# Schematic.net
KiCad netlist of a schematic drawn in EasyEDA
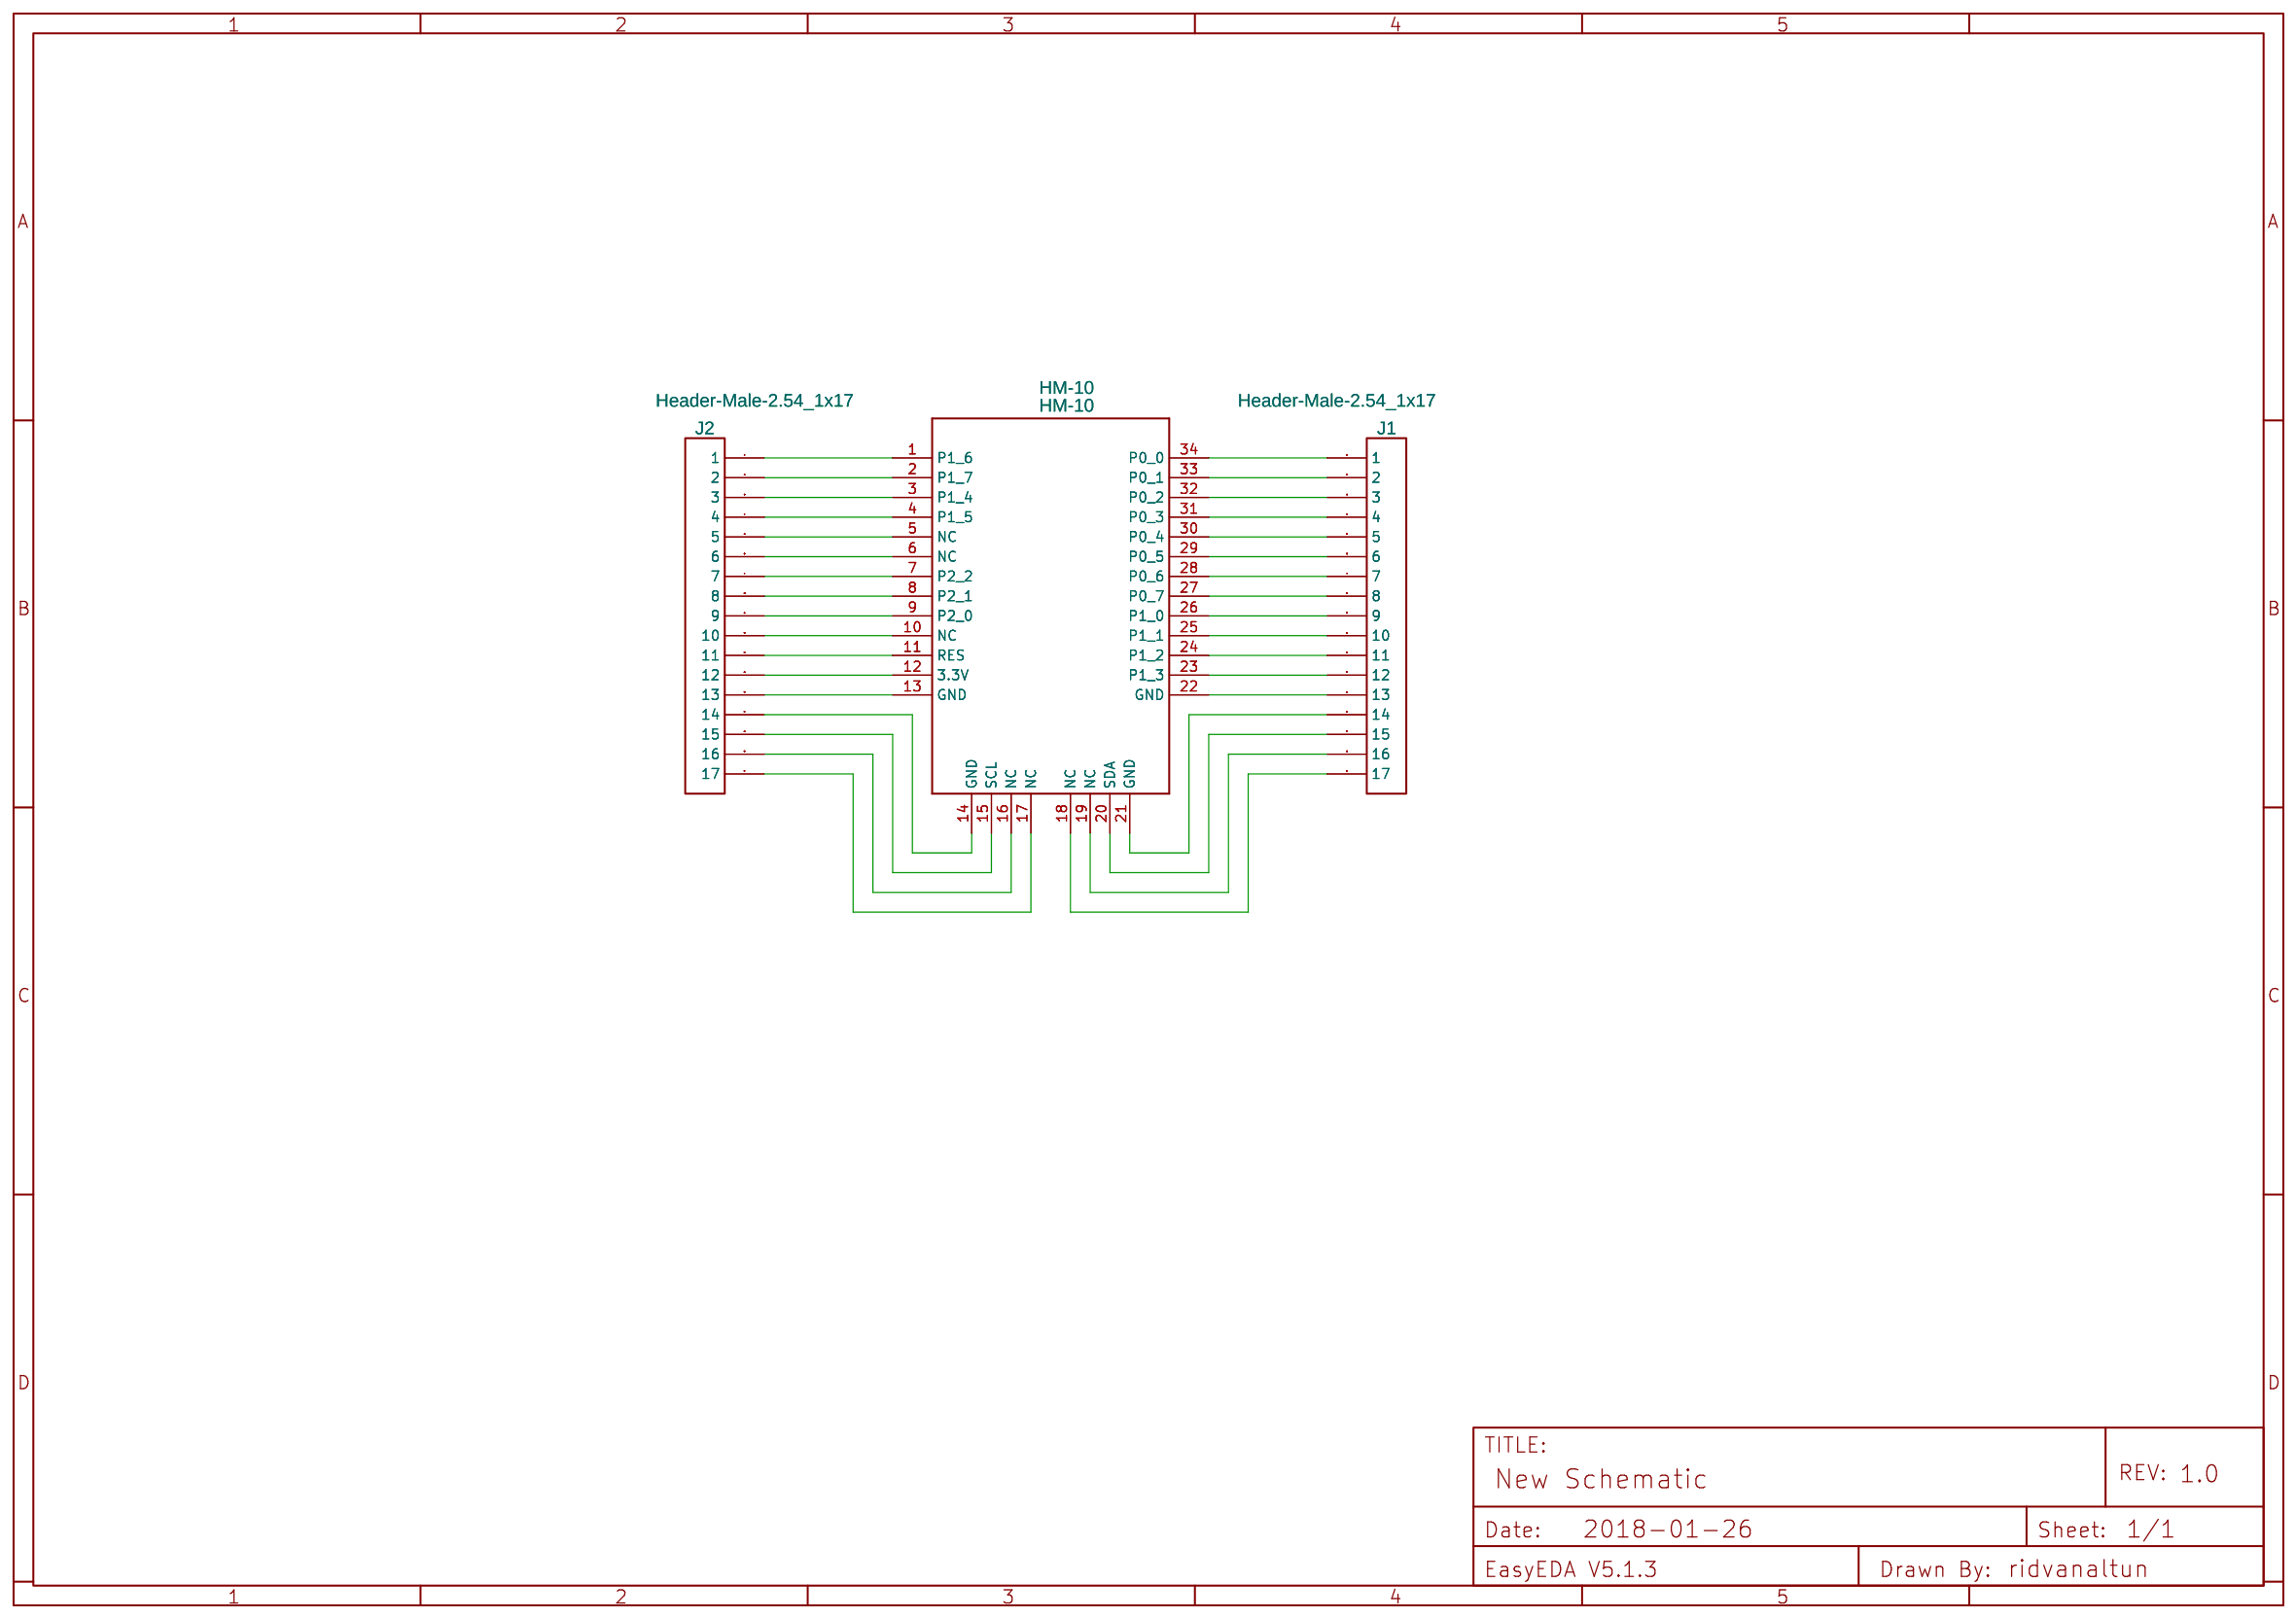
[diagram p0: schematic sheet]

(export (version "E")
  (design (tool "Eeschema 10.0.6"))
  (components
    (comp (ref "HM-10")
      (value "HM-10")
      (fields (field (name "BOM_Manufacturer Part") "?"))
      (libsource (lib "") (part "Unknown_525_315"))
    )
    (comp (ref "J1")
      (value "Header-Male-2.54_1x17")
      (fields (field (name "BOM_Manufacturer Part") "2.54mm 1*17PHeader"))
      (libsource (lib "") (part "Unknown_675_315"))
    )
    (comp (ref "J2")
      (value "Header-Male-2.54_1x17")
      (fields (field (name "BOM_Manufacturer Part") "2.54mm 1*17PHeader"))
      (libsource (lib "") (part "Unknown_370_315"))
    )
  )
  (nets
    (net (code "1") (name "Net-(HM-10-3.3V)") (class "Default")
      (node (ref "HM-10") (pin "12") (pinfunction "3.3V_12") (pintype "unspecified"))
      (node (ref "J2") (pin "12") (pinfunction "12_12") (pintype "input"))
    )
    (net (code "2") (name "Net-(HM-10-GND-Pad13)") (class "Default")
      (node (ref "HM-10") (pin "13") (pinfunction "GND_13") (pintype "unspecified"))
      (node (ref "J2") (pin "13") (pinfunction "13_13") (pintype "input"))
    )
    (net (code "3") (name "Net-(HM-10-GND-Pad14)") (class "Default")
      (node (ref "HM-10") (pin "14") (pinfunction "GND_14") (pintype "unspecified"))
      (node (ref "J2") (pin "14") (pinfunction "14_14") (pintype "input"))
    )
    (net (code "4") (name "Net-(HM-10-GND-Pad21)") (class "Default")
      (node (ref "HM-10") (pin "21") (pinfunction "GND_21") (pintype "unspecified"))
      (node (ref "J1") (pin "14") (pinfunction "14_14") (pintype "input"))
    )
    (net (code "5") (name "Net-(HM-10-GND-Pad22)") (class "Default")
      (node (ref "HM-10") (pin "22") (pinfunction "GND_22") (pintype "unspecified"))
      (node (ref "J1") (pin "13") (pinfunction "13_13") (pintype "input"))
    )
    (net (code "6") (name "Net-(HM-10-NC-Pad5)") (class "Default")
      (node (ref "HM-10") (pin "5") (pinfunction "NC_5") (pintype "unspecified"))
      (node (ref "J2") (pin "5") (pinfunction "5_5") (pintype "input"))
    )
    (net (code "7") (name "Net-(HM-10-NC-Pad6)") (class "Default")
      (node (ref "HM-10") (pin "6") (pinfunction "NC_6") (pintype "unspecified"))
      (node (ref "J2") (pin "6") (pinfunction "6_6") (pintype "input"))
    )
    (net (code "8") (name "Net-(HM-10-NC-Pad10)") (class "Default")
      (node (ref "HM-10") (pin "10") (pinfunction "NC_10") (pintype "unspecified"))
      (node (ref "J2") (pin "10") (pinfunction "10_10") (pintype "input"))
    )
    (net (code "9") (name "Net-(HM-10-NC-Pad16)") (class "Default")
      (node (ref "HM-10") (pin "16") (pinfunction "NC_16") (pintype "unspecified"))
      (node (ref "J2") (pin "16") (pinfunction "16_16") (pintype "input"))
    )
    (net (code "10") (name "Net-(HM-10-NC-Pad17)") (class "Default")
      (node (ref "HM-10") (pin "17") (pinfunction "NC_17") (pintype "unspecified"))
      (node (ref "J2") (pin "17") (pinfunction "17_17") (pintype "input"))
    )
    (net (code "11") (name "Net-(HM-10-NC-Pad18)") (class "Default")
      (node (ref "HM-10") (pin "18") (pinfunction "NC_18") (pintype "unspecified"))
      (node (ref "J1") (pin "17") (pinfunction "17_17") (pintype "input"))
    )
    (net (code "12") (name "Net-(HM-10-NC-Pad19)") (class "Default")
      (node (ref "HM-10") (pin "19") (pinfunction "NC_19") (pintype "unspecified"))
      (node (ref "J1") (pin "16") (pinfunction "16_16") (pintype "input"))
    )
    (net (code "13") (name "Net-(HM-10-P0_0)") (class "Default")
      (node (ref "HM-10") (pin "34") (pinfunction "P0_0_34") (pintype "unspecified"))
      (node (ref "J1") (pin "1") (pinfunction "1_1") (pintype "input"))
    )
    (net (code "14") (name "Net-(HM-10-P0_1)") (class "Default")
      (node (ref "HM-10") (pin "33") (pinfunction "P0_1_33") (pintype "unspecified"))
      (node (ref "J1") (pin "2") (pinfunction "2_2") (pintype "input"))
    )
    (net (code "15") (name "Net-(HM-10-P0_2)") (class "Default")
      (node (ref "HM-10") (pin "32") (pinfunction "P0_2_32") (pintype "unspecified"))
      (node (ref "J1") (pin "3") (pinfunction "3_3") (pintype "input"))
    )
    (net (code "16") (name "Net-(HM-10-P0_3)") (class "Default")
      (node (ref "HM-10") (pin "31") (pinfunction "P0_3_31") (pintype "unspecified"))
      (node (ref "J1") (pin "4") (pinfunction "4_4") (pintype "input"))
    )
    (net (code "17") (name "Net-(HM-10-P0_4)") (class "Default")
      (node (ref "HM-10") (pin "30") (pinfunction "P0_4_30") (pintype "unspecified"))
      (node (ref "J1") (pin "5") (pinfunction "5_5") (pintype "input"))
    )
    (net (code "18") (name "Net-(HM-10-P0_5)") (class "Default")
      (node (ref "HM-10") (pin "29") (pinfunction "P0_5_29") (pintype "unspecified"))
      (node (ref "J1") (pin "6") (pinfunction "6_6") (pintype "input"))
    )
    (net (code "19") (name "Net-(HM-10-P0_6)") (class "Default")
      (node (ref "HM-10") (pin "28") (pinfunction "P0_6_28") (pintype "unspecified"))
      (node (ref "J1") (pin "7") (pinfunction "7_7") (pintype "input"))
    )
    (net (code "20") (name "Net-(HM-10-P0_7)") (class "Default")
      (node (ref "HM-10") (pin "27") (pinfunction "P0_7_27") (pintype "unspecified"))
      (node (ref "J1") (pin "8") (pinfunction "8_8") (pintype "input"))
    )
    (net (code "21") (name "Net-(HM-10-P1_0)") (class "Default")
      (node (ref "HM-10") (pin "26") (pinfunction "P1_0_26") (pintype "unspecified"))
      (node (ref "J1") (pin "9") (pinfunction "9_9") (pintype "input"))
    )
    (net (code "22") (name "Net-(HM-10-P1_1)") (class "Default")
      (node (ref "HM-10") (pin "25") (pinfunction "P1_1_25") (pintype "unspecified"))
      (node (ref "J1") (pin "10") (pinfunction "10_10") (pintype "input"))
    )
    (net (code "23") (name "Net-(HM-10-P1_2)") (class "Default")
      (node (ref "HM-10") (pin "24") (pinfunction "P1_2_24") (pintype "unspecified"))
      (node (ref "J1") (pin "11") (pinfunction "11_11") (pintype "input"))
    )
    (net (code "24") (name "Net-(HM-10-P1_3)") (class "Default")
      (node (ref "HM-10") (pin "23") (pinfunction "P1_3_23") (pintype "unspecified"))
      (node (ref "J1") (pin "12") (pinfunction "12_12") (pintype "input"))
    )
    (net (code "25") (name "Net-(HM-10-P1_4)") (class "Default")
      (node (ref "HM-10") (pin "3") (pinfunction "P1_4_3") (pintype "unspecified"))
      (node (ref "J2") (pin "3") (pinfunction "3_3") (pintype "input"))
    )
    (net (code "26") (name "Net-(HM-10-P1_5)") (class "Default")
      (node (ref "HM-10") (pin "4") (pinfunction "P1_5_4") (pintype "unspecified"))
      (node (ref "J2") (pin "4") (pinfunction "4_4") (pintype "input"))
    )
    (net (code "27") (name "Net-(HM-10-P1_6)") (class "Default")
      (node (ref "HM-10") (pin "1") (pinfunction "P1_6_1") (pintype "unspecified"))
      (node (ref "J2") (pin "1") (pinfunction "1_1") (pintype "input"))
    )
    (net (code "28") (name "Net-(HM-10-P1_7)") (class "Default")
      (node (ref "HM-10") (pin "2") (pinfunction "P1_7_2") (pintype "unspecified"))
      (node (ref "J2") (pin "2") (pinfunction "2_2") (pintype "input"))
    )
    (net (code "29") (name "Net-(HM-10-P2_0)") (class "Default")
      (node (ref "HM-10") (pin "9") (pinfunction "P2_0_9") (pintype "unspecified"))
      (node (ref "J2") (pin "9") (pinfunction "9_9") (pintype "input"))
    )
    (net (code "30") (name "Net-(HM-10-P2_1)") (class "Default")
      (node (ref "HM-10") (pin "8") (pinfunction "P2_1_8") (pintype "unspecified"))
      (node (ref "J2") (pin "8") (pinfunction "8_8") (pintype "input"))
    )
    (net (code "31") (name "Net-(HM-10-P2_2)") (class "Default")
      (node (ref "HM-10") (pin "7") (pinfunction "P2_2_7") (pintype "unspecified"))
      (node (ref "J2") (pin "7") (pinfunction "7_7") (pintype "input"))
    )
    (net (code "32") (name "Net-(HM-10-RES)") (class "Default")
      (node (ref "HM-10") (pin "11") (pinfunction "RES_11") (pintype "unspecified"))
      (node (ref "J2") (pin "11") (pinfunction "11_11") (pintype "input"))
    )
    (net (code "33") (name "Net-(HM-10-SCL)") (class "Default")
      (node (ref "HM-10") (pin "15") (pinfunction "SCL_15") (pintype "unspecified"))
      (node (ref "J2") (pin "15") (pinfunction "15_15") (pintype "input"))
    )
    (net (code "34") (name "Net-(HM-10-SDA)") (class "Default")
      (node (ref "HM-10") (pin "20") (pinfunction "SDA_20") (pintype "unspecified"))
      (node (ref "J1") (pin "15") (pinfunction "15_15") (pintype "input"))
    )
  )
)
